# 07_E_ink_display_Button_control.net
KiCad netlist of a schematic drawn in Altium Designer
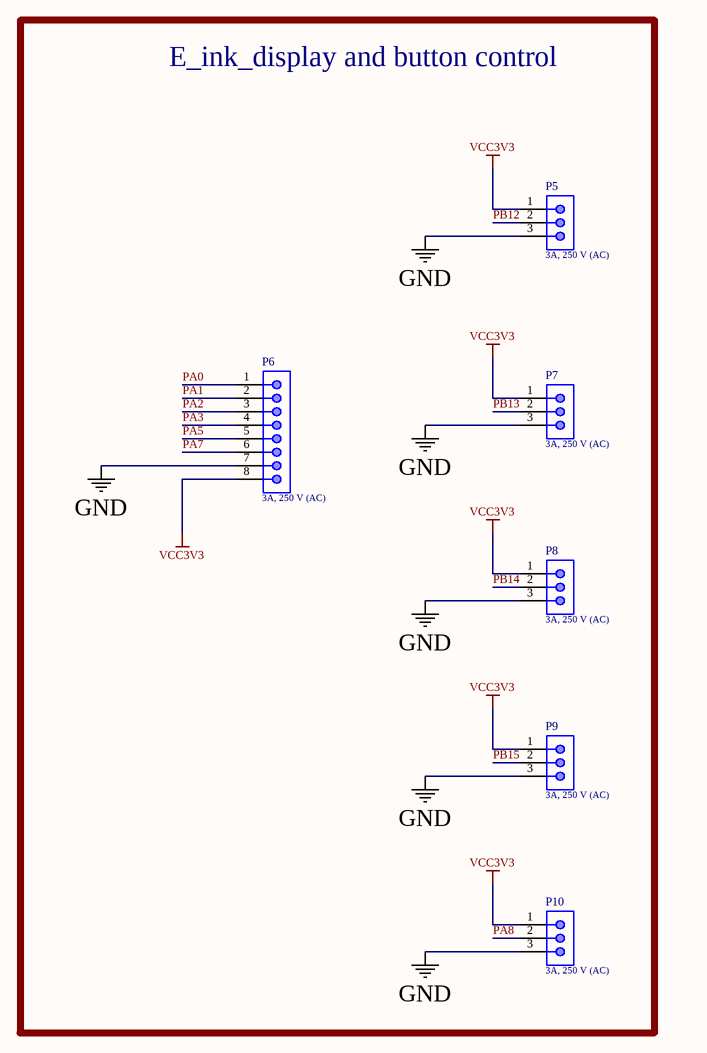
[diagram p0: 07_E_ink_display_Button_control.SchDoc]

(export (version "E")
  (design (tool "Eeschema 10.0.6"))
  (components
    (comp (ref "P5")
      (value "3A, 250 V (AC)")
      (footprint "61300311121")
      (description "WR-PHD Pin Header, THT, pitch 2.54mm, Single Row, Vertical, 3p")
      (fields
        (field (name "MANUFACTURER PART NUMBER") "61300311121")
        (field (name "MANUFACTURER") "Wurth Elektronik")
      )
      (libsource (lib "WR-PHD_Pin Header_2.54mm") (part "61300311121"))
    )
    (comp (ref "P6")
      (value "3A, 250 V (AC)")
      (footprint "61300811121")
      (description "WR-PHD Pin Header, THT, pitch 2.54mm, Single Row, Vertical, 8p")
      (fields
        (field (name "MANUFACTURER PART NUMBER") "61300811121")
        (field (name "MANUFACTURER") "Wurth Elektronik")
      )
      (libsource (lib "WR-PHD_Pin Header_2.54mm") (part "61300811121"))
    )
    (comp (ref "P7")
      (value "3A, 250 V (AC)")
      (footprint "61300311121")
      (description "WR-PHD Pin Header, THT, pitch 2.54mm, Single Row, Vertical, 3p")
      (fields
        (field (name "MANUFACTURER PART NUMBER") "61300311121")
        (field (name "MANUFACTURER") "Wurth Elektronik")
      )
      (libsource (lib "WR-PHD_Pin Header_2.54mm") (part "61300311121"))
    )
    (comp (ref "P8")
      (value "3A, 250 V (AC)")
      (footprint "61300311121")
      (description "WR-PHD Pin Header, THT, pitch 2.54mm, Single Row, Vertical, 3p")
      (fields
        (field (name "MANUFACTURER PART NUMBER") "61300311121")
        (field (name "MANUFACTURER") "Wurth Elektronik")
      )
      (libsource (lib "WR-PHD_Pin Header_2.54mm") (part "61300311121"))
    )
    (comp (ref "P9")
      (value "3A, 250 V (AC)")
      (footprint "61300311121")
      (description "WR-PHD Pin Header, THT, pitch 2.54mm, Single Row, Vertical, 3p")
      (fields
        (field (name "MANUFACTURER PART NUMBER") "61300311121")
        (field (name "MANUFACTURER") "Wurth Elektronik")
      )
      (libsource (lib "WR-PHD_Pin Header_2.54mm") (part "61300311121"))
    )
    (comp (ref "P10")
      (value "3A, 250 V (AC)")
      (footprint "61300311121")
      (description "WR-PHD Pin Header, THT, pitch 2.54mm, Single Row, Vertical, 3p")
      (fields
        (field (name "MANUFACTURER PART NUMBER") "61300311121")
        (field (name "MANUFACTURER") "Wurth Elektronik")
      )
      (libsource (lib "WR-PHD_Pin Header_2.54mm") (part "61300311121"))
    )
  )
  (nets
    (net (code "1") (name "/PA0") (class "Default")
      (node (ref "P6") (pin "1") (pinfunction "1_1") (pintype "passive"))
    )
    (net (code "2") (name "/PA1") (class "Default")
      (node (ref "P6") (pin "2") (pinfunction "2_2") (pintype "passive"))
    )
    (net (code "3") (name "/PA2") (class "Default")
      (node (ref "P6") (pin "3") (pinfunction "3_3") (pintype "passive"))
    )
    (net (code "4") (name "/PA3") (class "Default")
      (node (ref "P6") (pin "4") (pinfunction "4_4") (pintype "passive"))
    )
    (net (code "5") (name "/PA5") (class "Default")
      (node (ref "P6") (pin "5") (pinfunction "5_5") (pintype "passive"))
    )
    (net (code "6") (name "/PA7") (class "Default")
      (node (ref "P6") (pin "6") (pinfunction "6_6") (pintype "passive"))
    )
    (net (code "7") (name "/PA8") (class "Default")
      (node (ref "P10") (pin "2") (pinfunction "2_2") (pintype "passive"))
    )
    (net (code "8") (name "/PB12") (class "Default")
      (node (ref "P5") (pin "2") (pinfunction "2_2") (pintype "passive"))
    )
    (net (code "9") (name "/PB13") (class "Default")
      (node (ref "P7") (pin "2") (pinfunction "2_2") (pintype "passive"))
    )
    (net (code "10") (name "/PB14") (class "Default")
      (node (ref "P8") (pin "2") (pinfunction "2_2") (pintype "passive"))
    )
    (net (code "11") (name "/PB15") (class "Default")
      (node (ref "P9") (pin "2") (pinfunction "2_2") (pintype "passive"))
    )
    (net (code "12") (name "GND") (class "Default")
      (node (ref "P10") (pin "3") (pinfunction "3_3") (pintype "passive"))
      (node (ref "P5") (pin "3") (pinfunction "3_3") (pintype "passive"))
      (node (ref "P6") (pin "7") (pinfunction "7_7") (pintype "passive"))
      (node (ref "P7") (pin "3") (pinfunction "3_3") (pintype "passive"))
      (node (ref "P8") (pin "3") (pinfunction "3_3") (pintype "passive"))
      (node (ref "P9") (pin "3") (pinfunction "3_3") (pintype "passive"))
    )
    (net (code "13") (name "VCC3V3") (class "Default")
      (node (ref "P10") (pin "1") (pinfunction "1_1") (pintype "passive"))
      (node (ref "P5") (pin "1") (pinfunction "1_1") (pintype "passive"))
      (node (ref "P6") (pin "8") (pinfunction "8_8") (pintype "passive"))
      (node (ref "P7") (pin "1") (pinfunction "1_1") (pintype "passive"))
      (node (ref "P8") (pin "1") (pinfunction "1_1") (pintype "passive"))
      (node (ref "P9") (pin "1") (pinfunction "1_1") (pintype "passive"))
    )
  )
)
